# Logic.net
KiCad netlist of a schematic drawn in Altium Designer
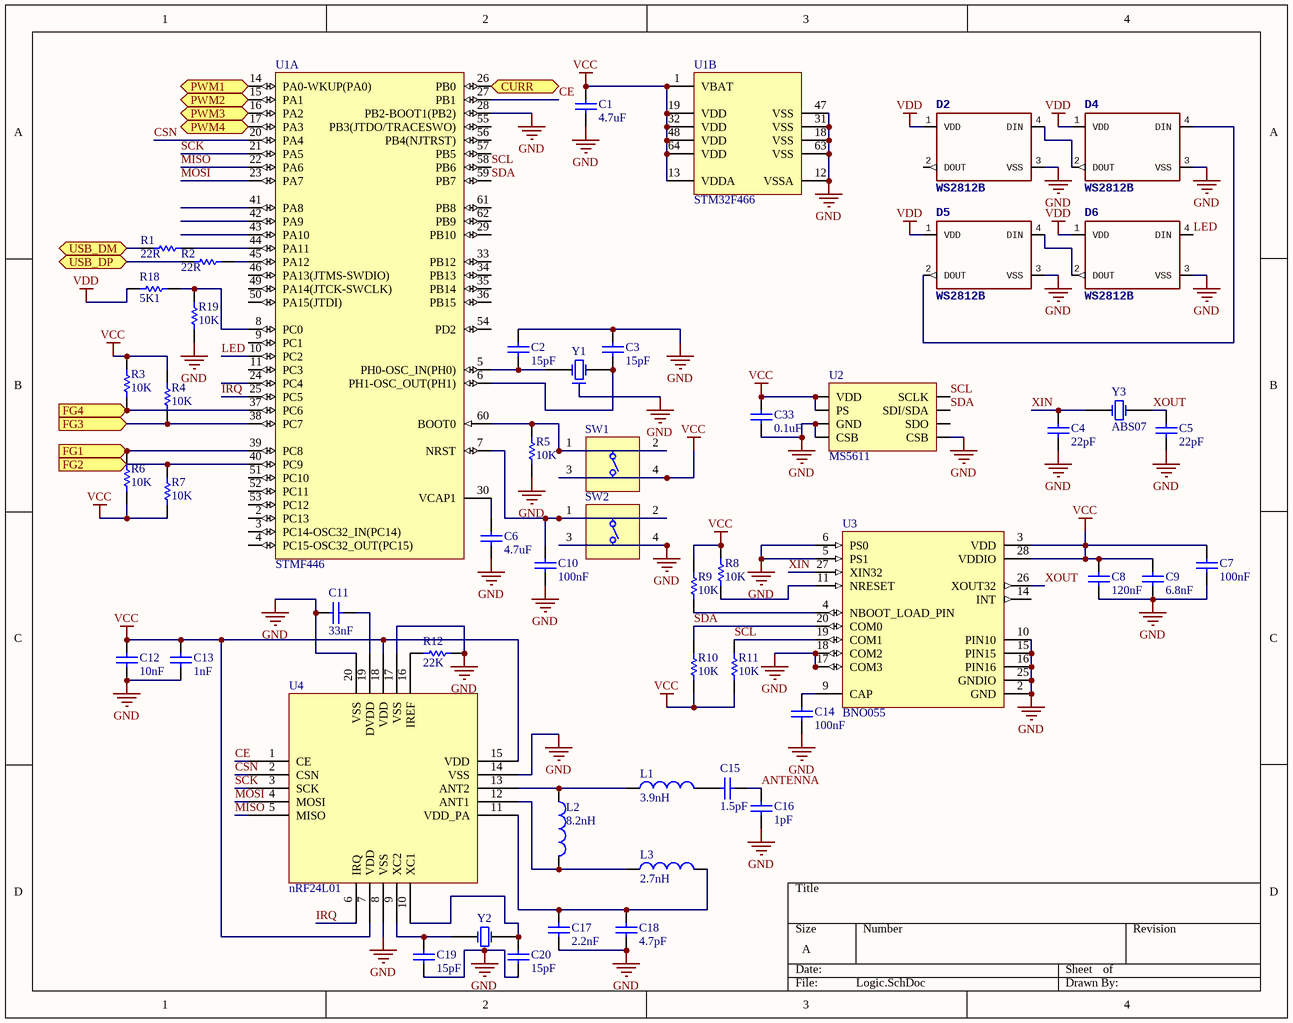
[diagram p0: Logic.SchDoc]

(export (version "E")
  (design (tool "Eeschema 10.0.6"))
  (components
    (comp (ref "C1")
      (value "4.7uF")
      (footprint "CAPC0402(1005)60_L")
      (description "CAP 4.7uF 6.3V ±10% 0402 (1005 Metric) Thickness 0.6mm SMD")
      (fields (field (name "TOLERANCE") "Â±10%"))
      (libsource (lib "Altium Content Vault") (part "CAP"))
    )
    (comp (ref "C2")
      (value "15pF")
      (footprint "CAPC0402(1005)60_M")
      (description "CAP 15pF 25V ±0.25pF 0402 (1005 Metric) Thickness 0.6mm SMD")
      (fields (field (name "TOLERANCE") "Â±0.25pF"))
      (libsource (lib "Altium Content Vault") (part "CMP-1034-00804-1"))
    )
    (comp (ref "C3")
      (value "15pF")
      (footprint "CAPC0402(1005)60_M")
      (description "CAP 15pF 25V ±0.25pF 0402 (1005 Metric) Thickness 0.6mm SMD")
      (fields (field (name "TOLERANCE") "Â±0.25pF"))
      (libsource (lib "Altium Content Vault") (part "CMP-1034-00804-1"))
    )
    (comp (ref "C4")
      (value "22pF")
      (footprint "CAPC0402(1005)60_L")
      (description "CAP 22pF 25V ±10% 0402 (1005 Metric) Thickness 0.6mm SMD")
      (fields (field (name "TOLERANCE") "Â±10%"))
      (libsource (lib "Altium Content Vault") (part "CAP"))
    )
    (comp (ref "C5")
      (value "22pF")
      (footprint "CAPC0402(1005)60_L")
      (description "CAP 22pF 25V ±10% 0402 (1005 Metric) Thickness 0.6mm SMD")
      (fields (field (name "TOLERANCE") "Â±10%"))
      (libsource (lib "Altium Content Vault") (part "CAP"))
    )
    (comp (ref "C6")
      (value "4.7uF")
      (footprint "CAPC0402(1005)60_L")
      (description "CAP 4.7uF 6.3V ±10% 0402 (1005 Metric) Thickness 0.6mm SMD")
      (fields (field (name "TOLERANCE") "Â±10%"))
      (libsource (lib "Altium Content Vault") (part "CMP-1034-02136-1"))
    )
    (comp (ref "C7")
      (value "100nF")
      (footprint "CAPC0402(1005)60_M")
      (description "CAP 100nF 6.3V ±5% 0402 (1005 Metric) Thickness 0.6mm SMD")
      (fields (field (name "TOLERANCE") "Â±5%"))
      (libsource (lib "Altium Content Vault") (part "CAP"))
    )
    (comp (ref "C8")
      (value "120nF")
      (footprint "CAPC0402(1005)60_M")
      (description "CAP 100nF 6.3V ±5% 0402 (1005 Metric) Thickness 0.6mm SMD")
      (fields (field (name "TOLERANCE") "Â±5%"))
      (libsource (lib "Altium Content Vault") (part "CAP"))
    )
    (comp (ref "C9")
      (value "6.8nF")
      (footprint "CAPC0402(1005)60_L")
      (description "CAP 6.8nF 6.3V ±5% 0402 (1005 Metric) Thickness 0.6mm SMD")
      (fields (field (name "TOLERANCE") "Â±5%"))
      (libsource (lib "Altium Content Vault") (part "CAP"))
    )
    (comp (ref "C10")
      (value "100nF")
      (footprint "CAPC0402(1005)60_M")
      (description "CAP 100nF 6.3V ±5% 0402 (1005 Metric) Thickness 0.6mm SMD")
      (fields (field (name "TOLERANCE") "Â±5%"))
      (libsource (lib "Altium Content Vault") (part "CAP"))
    )
    (comp (ref "C11")
      (value "33nF")
      (footprint "CAPC0402(1005)60_M")
      (description "CAP 33nF 6.3V ±10% 0402 (1005 Metric) Thickness 0.6mm SMD")
      (fields (field (name "TOLERANCE") "Â±10%"))
      (libsource (lib "Altium Content Vault") (part "CAP"))
    )
    (comp (ref "C12")
      (value "10nF")
      (footprint "CAPC0402(1005)60_M")
      (description "CAP 10nF 6.3V ±5% 0402 (1005 Metric) Thickness 0.6mm SMD")
      (fields (field (name "TOLERANCE") "Â±5%"))
      (libsource (lib "Altium Content Vault") (part "CAP"))
    )
    (comp (ref "C13")
      (value "1nF")
      (footprint "CAPC0402(1005)60_M")
      (description "CAP 1nF 6.3V ±5% 0402 (1005 Metric) Thickness 0.6mm SMD")
      (fields (field (name "TOLERANCE") "Â±5%"))
      (libsource (lib "Altium Content Vault") (part "CAP"))
    )
    (comp (ref "C14")
      (value "100nF")
      (footprint "CAPC0402(1005)60_M")
      (description "CAP 100nF 6.3V ±5% 0402 (1005 Metric) Thickness 0.6mm SMD")
      (fields (field (name "TOLERANCE") "Â±5%"))
      (libsource (lib "Altium Content Vault") (part "CAP"))
    )
    (comp (ref "C15")
      (value "1.5pF")
      (footprint "CAPC0402(1005)60_L")
      (description "CAP 1.5pF 25V ±0.5pF 0402 (1005 Metric) Thickness 0.6mm SMD")
      (fields (field (name "TOLERANCE") "Â±0.5pF"))
      (libsource (lib "Altium Content Vault") (part "CAP"))
    )
    (comp (ref "C16")
      (value "1pF")
      (footprint "CAPC0402(1005)60_M")
      (description "CAP 1pF 25V ±0.5pF 0402 (1005 Metric) Thickness 0.6mm SMD")
      (fields (field (name "TOLERANCE") "Â±0.5pF"))
      (libsource (lib "Altium Content Vault") (part "CAP"))
    )
    (comp (ref "C17")
      (value "2.2nF")
      (footprint "CAPC0402(1005)60_N")
      (description "CAP 2.2nF 6.3V ±5% 0402 (1005 Metric) Thickness 0.6mm SMD")
      (fields (field (name "TOLERANCE") "Â±5%"))
      (libsource (lib "Altium Content Vault") (part "CAP"))
    )
    (comp (ref "C18")
      (value "4.7pF")
      (footprint "CAPC0402(1005)60_M")
      (description "CAP 4.7pF 25V ±0.1pF 0402 (1005 Metric) Thickness 0.6mm SMD")
      (fields (field (name "TOLERANCE") "Â±0.1pF"))
      (libsource (lib "Altium Content Vault") (part "CAP"))
    )
    (comp (ref "C19")
      (value "15pF")
      (footprint "CAPC0402(1005)60_N")
      (description "CAP 15pF 25V ±10% 0402 (1005 Metric) Thickness 0.6mm SMD")
      (fields (field (name "TOLERANCE") "Â±10%"))
      (libsource (lib "Altium Content Vault") (part "CAP"))
    )
    (comp (ref "C20")
      (value "15pF")
      (footprint "CAPC0402(1005)60_N")
      (description "CAP 15pF 25V ±10% 0402 (1005 Metric) Thickness 0.6mm SMD")
      (fields (field (name "TOLERANCE") "Â±10%"))
      (libsource (lib "Altium Content Vault") (part "CMP-1034-00809-1"))
    )
    (comp (ref "C33")
      (value "0.1uF")
      (footprint "CAPC0402(1005)60_M")
      (description "CAP 100nF 6.3V ±5% 0402 (1005 Metric) Thickness 0.6mm SMD")
      (fields (field (name "TOLERANCE") "Â±5%"))
      (libsource (lib "Altium Content Vault") (part "CAP"))
    )
    (comp (ref "D2") (value "WS2812B") (footprint "WS2812B") (libsource (lib "Components") (part "WS2812B")))
    (comp (ref "D4") (value "WS2812B") (footprint "WS2812B") (libsource (lib "Components") (part "WS2812B")))
    (comp (ref "D5") (value "WS2812B") (footprint "WS2812B") (libsource (lib "Components") (part "WS2812B")))
    (comp (ref "D6") (value "WS2812B") (footprint "WS2812B") (libsource (lib "Components") (part "WS2812B")))
    (comp (ref "L1")
      (value "3.9nH")
      (footprint "INDC0402(1005)_N")
      (description "Inductor")
      (fields (field (name "PUBLISHER") "Altium Limited"))
      (libsource (lib "Components") (part "INDC0402"))
    )
    (comp (ref "L2")
      (value "8.2nH")
      (footprint "INDC0402(1005)_N")
      (description "Inductor")
      (fields (field (name "PUBLISHER") "Altium Limited"))
      (libsource (lib "Components") (part "INDC0402"))
    )
    (comp (ref "L3")
      (value "2.7nH")
      (footprint "INDC0402(1005)_N")
      (description "Inductor")
      (fields (field (name "PUBLISHER") "Altium Limited"))
      (libsource (lib "Components") (part "INDC0402"))
    )
    (comp (ref "R1")
      (value "22R")
      (footprint "RESC0402(1005)_M")
      (description "22R 0.063W 5% 0402 (1005 Metric)  SMD")
      (fields (field (name "POWER") "0.063 W") (field (name "TOLERANCE") "5 %"))
      (libsource (lib "Altium Content Vault") (part "RES"))
    )
    (comp (ref "R2")
      (value "22R")
      (footprint "RESC0402(1005)_M")
      (description "22R 0.063W 5% 0402 (1005 Metric)  SMD")
      (fields (field (name "POWER") "0.063 W") (field (name "TOLERANCE") "5 %"))
      (libsource (lib "Altium Content Vault") (part "RES"))
    )
    (comp (ref "R3")
      (value "10K")
      (footprint "RESC0402(1005)_N")
      (description "10K 0.063W 5% 0402 (1005 Metric)  SMD")
      (fields (field (name "TOLERANCE") "5 %") (field (name "POWER") "0.063 W"))
      (libsource (lib "Altium Content Vault") (part "RES"))
    )
    (comp (ref "R4")
      (value "10K")
      (footprint "RESC0402(1005)_N")
      (description "10K 0.063W 5% 0402 (1005 Metric)  SMD")
      (fields (field (name "TOLERANCE") "5 %") (field (name "POWER") "0.063 W"))
      (libsource (lib "Altium Content Vault") (part "RES"))
    )
    (comp (ref "R5")
      (value "10K")
      (footprint "RESC0402(1005)_N")
      (description "10K 0.063W 5% 0402 (1005 Metric)  SMD")
      (fields (field (name "TOLERANCE") "5 %") (field (name "POWER") "0.063 W"))
      (libsource (lib "Altium Content Vault") (part "RES"))
    )
    (comp (ref "R6")
      (value "10K")
      (footprint "RESC0402(1005)_N")
      (description "10K 0.063W 5% 0402 (1005 Metric)  SMD")
      (fields (field (name "TOLERANCE") "5 %") (field (name "POWER") "0.063 W"))
      (libsource (lib "Altium Content Vault") (part "RES"))
    )
    (comp (ref "R7")
      (value "10K")
      (footprint "RESC0402(1005)_N")
      (description "10K 0.063W 5% 0402 (1005 Metric)  SMD")
      (fields (field (name "TOLERANCE") "5 %") (field (name "POWER") "0.063 W"))
      (libsource (lib "Altium Content Vault") (part "RES"))
    )
    (comp (ref "R8")
      (value "10K")
      (footprint "RESC0402(1005)_N")
      (description "10K 0.063W 5% 0402 (1005 Metric)  SMD")
      (fields (field (name "TOLERANCE") "5 %") (field (name "POWER") "0.063 W"))
      (libsource (lib "Altium Content Vault") (part "RES"))
    )
    (comp (ref "R9")
      (value "10K")
      (footprint "RESC0402(1005)_N")
      (description "10K 0.063W 5% 0402 (1005 Metric)  SMD")
      (fields (field (name "TOLERANCE") "5 %") (field (name "POWER") "0.063 W"))
      (libsource (lib "Altium Content Vault") (part "RES"))
    )
    (comp (ref "R10")
      (value "10K")
      (footprint "RESC0402(1005)_N")
      (description "10K 0.063W 5% 0402 (1005 Metric)  SMD")
      (fields (field (name "TOLERANCE") "5 %") (field (name "POWER") "0.063 W"))
      (libsource (lib "Altium Content Vault") (part "RES"))
    )
    (comp (ref "R11")
      (value "10K")
      (footprint "RESC0402(1005)_N")
      (description "10K 0.063W 5% 0402 (1005 Metric)  SMD")
      (fields (field (name "TOLERANCE") "5 %") (field (name "POWER") "0.063 W"))
      (libsource (lib "Altium Content Vault") (part "RES"))
    )
    (comp (ref "R12")
      (value "22K")
      (footprint "RESC0402(1005)_L")
      (description "22K 0.063W 5% 0402 (1005 Metric)  SMD")
      (fields (field (name "TOLERANCE") "5 %") (field (name "POWER") "0.063 W"))
      (libsource (lib "Altium Content Vault") (part "RES"))
    )
    (comp (ref "R18")
      (value "5K1")
      (footprint "RESC0402(1005)_L")
      (description "5K1 0.063W 5% 0402 (1005 Metric)  SMD")
      (fields (field (name "TOLERANCE") "5 %") (field (name "POWER") "0.063 W"))
      (libsource (lib "Altium Content Vault") (part "RES"))
    )
    (comp (ref "R19")
      (value "10K")
      (footprint "RESC0402(1005)_N")
      (description "10K 0.063W 5% 0402 (1005 Metric)  SMD")
      (fields (field (name "TOLERANCE") "5 %") (field (name "POWER") "0.063 W"))
      (libsource (lib "Altium Content Vault") (part "RES"))
    )
    (comp (ref "SW1")
      (value "~")
      (footprint "SWITCH")
      (description "Switch, SPNO Push Button SMD")
      (fields (field (name "MANUFACTURER") "Diptronics") (field (name "PARTNUMBER") "DTSM-61NT/R"))
      (libsource (lib "altium-import") (part "root_0_DIPT-DTSM-6_"))
    )
    (comp (ref "SW2")
      (value "~")
      (footprint "SWITCH")
      (description "Switch, SPNO Push Button SMD")
      (fields (field (name "MANUFACTURER") "Diptronics") (field (name "PARTNUMBER") "DTSM-61NT/R"))
      (libsource (lib "altium-import") (part "root_0_DIPT-DTSM-6_"))
    )
    (comp (ref "U1")
      (value "STMF446")
      (footprint "STM-LQFP64_N")
      (libsource (lib "Components") (part "MC-ARM-STM32F4X5-SQ64"))
    )
    (comp (ref "U2") (value "MS5611") (footprint "MS5611") (libsource (lib "Components") (part "MS5611")))
    (comp (ref "U3")
      (value "BNO055")
      (footprint "LGA28R50P4X10_380X520X100")
      (libsource (lib "Components") (part "BNO055"))
    )
    (comp (ref "U4") (value "~") (footprint "QFN20") (libsource (lib "Components") (part "NRF24L01+")))
    (comp (ref "Y1")
      (value "~")
      (footprint "ABRA-ABM3B-4_V")
      (libsource (lib "Components") (part "ABRA-ABM3B-4"))
    )
    (comp (ref "Y2")
      (value "~")
      (footprint "ABRA-ABM3B-4_V")
      (libsource (lib "Components") (part "ABRA-ABM3B-4"))
    )
    (comp (ref "Y3") (value "ABS07") (footprint "ABS07") (libsource (lib "Components") (part "ABS07")))
  )
  (nets
    (net (code "1") (name "/ANTENNA") (class "Default")
      (node (ref "C15") (pin "2") (pinfunction "2_2") (pintype "passive"))
      (node (ref "C16") (pin "2") (pinfunction "2_2") (pintype "passive"))
    )
    (net (code "2") (name "/CE") (class "Default")
      (node (ref "U1") (pin "27") (pinfunction "PB1_27") (pintype "bidirectional"))
      (node (ref "U4") (pin "1") (pinfunction "CE_1") (pintype "passive"))
    )
    (net (code "3") (name "/CSN") (class "Default")
      (node (ref "U1") (pin "20") (pinfunction "PA4_20") (pintype "bidirectional"))
      (node (ref "U4") (pin "2") (pinfunction "CSN_2") (pintype "passive"))
    )
    (net (code "4") (name "/CURR") (class "Default")
      (node (ref "U1") (pin "26") (pinfunction "PB0_26") (pintype "bidirectional"))
    )
    (net (code "5") (name "/FG1") (class "Default")
      (node (ref "R6") (pin "2") (pinfunction "2_2") (pintype "passive"))
      (node (ref "U1") (pin "39") (pinfunction "PC8_39") (pintype "bidirectional"))
    )
    (net (code "6") (name "/FG2") (class "Default")
      (node (ref "R7") (pin "2") (pinfunction "2_2") (pintype "passive"))
      (node (ref "U1") (pin "40") (pinfunction "PC9_40") (pintype "bidirectional"))
    )
    (net (code "7") (name "/FG3") (class "Default")
      (node (ref "R4") (pin "1") (pinfunction "1_1") (pintype "passive"))
      (node (ref "U1") (pin "38") (pinfunction "PC7_38") (pintype "bidirectional"))
    )
    (net (code "8") (name "/FG4") (class "Default")
      (node (ref "R3") (pin "1") (pinfunction "1_1") (pintype "passive"))
      (node (ref "U1") (pin "37") (pinfunction "PC6_37") (pintype "bidirectional"))
    )
    (net (code "9") (name "/IRQ") (class "Default")
      (node (ref "U1") (pin "25") (pinfunction "PC5_25") (pintype "bidirectional"))
      (node (ref "U4") (pin "6") (pinfunction "IRQ_6") (pintype "passive"))
    )
    (net (code "10") (name "/LED") (class "Default")
      (node (ref "D6") (pin "4") (pinfunction "DIN_4") (pintype "passive"))
      (node (ref "U1") (pin "10") (pinfunction "PC2_10") (pintype "bidirectional"))
    )
    (net (code "11") (name "/MISO") (class "Default")
      (node (ref "U1") (pin "22") (pinfunction "PA6_22") (pintype "bidirectional"))
      (node (ref "U4") (pin "5") (pinfunction "MISO_5") (pintype "passive"))
    )
    (net (code "12") (name "/MOSI") (class "Default")
      (node (ref "U1") (pin "23") (pinfunction "PA7_23") (pintype "bidirectional"))
      (node (ref "U4") (pin "4") (pinfunction "MOSI_4") (pintype "passive"))
    )
    (net (code "13") (name "/PWM1") (class "Default")
      (node (ref "U1") (pin "14") (pinfunction "PA0-WKUP(PA0)_14") (pintype "bidirectional"))
    )
    (net (code "14") (name "/PWM2") (class "Default")
      (node (ref "U1") (pin "15") (pinfunction "PA1_15") (pintype "bidirectional"))
    )
    (net (code "15") (name "/PWM3") (class "Default")
      (node (ref "U1") (pin "16") (pinfunction "PA2_16") (pintype "bidirectional"))
    )
    (net (code "16") (name "/PWM4") (class "Default")
      (node (ref "U1") (pin "17") (pinfunction "PA3_17") (pintype "bidirectional"))
    )
    (net (code "17") (name "/SCK") (class "Default")
      (node (ref "U1") (pin "21") (pinfunction "PA5_21") (pintype "bidirectional"))
      (node (ref "U4") (pin "3") (pinfunction "SCK_3") (pintype "passive"))
    )
    (net (code "18") (name "/SCL") (class "Default")
      (node (ref "R11") (pin "2") (pinfunction "2_2") (pintype "passive"))
      (node (ref "U1") (pin "58") (pinfunction "PB6_58") (pintype "bidirectional"))
      (node (ref "U2") (pin "8") (pinfunction "SCLK_8") (pintype "passive"))
      (node (ref "U3") (pin "19") (pinfunction "COM1_19") (pintype "bidirectional"))
    )
    (net (code "19") (name "/SDA") (class "Default")
      (node (ref "R10") (pin "2") (pinfunction "2_2") (pintype "passive"))
      (node (ref "U1") (pin "59") (pinfunction "PB7_59") (pintype "bidirectional"))
      (node (ref "U2") (pin "7") (pinfunction "SDI/SDA_7") (pintype "passive"))
      (node (ref "U3") (pin "20") (pinfunction "COM0_20") (pintype "bidirectional"))
    )
    (net (code "20") (name "/USB_DM") (class "Default")
      (node (ref "R1") (pin "1") (pinfunction "1_1") (pintype "passive"))
    )
    (net (code "21") (name "/USB_DP") (class "Default")
      (node (ref "R2") (pin "1") (pinfunction "1_1") (pintype "passive"))
    )
    (net (code "22") (name "/XIN") (class "Default")
      (node (ref "C4") (pin "2") (pinfunction "2_2") (pintype "passive"))
      (node (ref "U3") (pin "27") (pinfunction "XIN32_27") (pintype "input"))
      (node (ref "Y3") (pin "1") (pinfunction "X1_1") (pintype "passive"))
    )
    (net (code "23") (name "/XOUT") (class "Default")
      (node (ref "C5") (pin "2") (pinfunction "2_2") (pintype "passive"))
      (node (ref "U3") (pin "26") (pinfunction "XOUT32_26") (pintype "output"))
      (node (ref "Y3") (pin "2") (pinfunction "X2_2") (pintype "passive"))
    )
    (net (code "24") (name "GND") (class "Default")
      (node (ref "C1") (pin "1") (pinfunction "1_1") (pintype "passive"))
      (node (ref "C10") (pin "1") (pinfunction "1_1") (pintype "passive"))
      (node (ref "C11") (pin "1") (pinfunction "1_1") (pintype "passive"))
      (node (ref "C12") (pin "1") (pinfunction "1_1") (pintype "passive"))
      (node (ref "C13") (pin "1") (pinfunction "1_1") (pintype "passive"))
      (node (ref "C14") (pin "1") (pinfunction "1_1") (pintype "passive"))
      (node (ref "C16") (pin "1") (pinfunction "1_1") (pintype "passive"))
      (node (ref "C17") (pin "1") (pinfunction "1_1") (pintype "passive"))
      (node (ref "C18") (pin "1") (pinfunction "1_1") (pintype "passive"))
      (node (ref "C19") (pin "1") (pinfunction "1_1") (pintype "passive"))
      (node (ref "C2") (pin "2") (pinfunction "2_2") (pintype "passive"))
      (node (ref "C20") (pin "1") (pinfunction "1_1") (pintype "passive"))
      (node (ref "C3") (pin "2") (pinfunction "2_2") (pintype "passive"))
      (node (ref "C33") (pin "1") (pinfunction "1_1") (pintype "passive"))
      (node (ref "C4") (pin "1") (pinfunction "1_1") (pintype "passive"))
      (node (ref "C5") (pin "1") (pinfunction "1_1") (pintype "passive"))
      (node (ref "C6") (pin "1") (pinfunction "1_1") (pintype "passive"))
      (node (ref "C7") (pin "1") (pinfunction "1_1") (pintype "passive"))
      (node (ref "C8") (pin "1") (pinfunction "1_1") (pintype "passive"))
      (node (ref "C9") (pin "1") (pinfunction "1_1") (pintype "passive"))
      (node (ref "D2") (pin "3") (pinfunction "VSS_3") (pintype "power_in"))
      (node (ref "D4") (pin "3") (pinfunction "VSS_3") (pintype "power_in"))
      (node (ref "D5") (pin "3") (pinfunction "VSS_3") (pintype "power_in"))
      (node (ref "D6") (pin "3") (pinfunction "VSS_3") (pintype "power_in"))
      (node (ref "R12") (pin "1") (pinfunction "1_1") (pintype "passive"))
      (node (ref "R19") (pin "1") (pinfunction "1_1") (pintype "passive"))
      (node (ref "R5") (pin "1") (pinfunction "1_1") (pintype "passive"))
      (node (ref "SW2") (pin "3") (pinfunction "T3_3") (pintype "passive"))
      (node (ref "SW2") (pin "4") (pinfunction "T3_4") (pintype "passive"))
      (node (ref "U1") (pin "12") (pinfunction "VSSA_12") (pintype "power_in"))
      (node (ref "U1") (pin "18") (pinfunction "VSS_18") (pintype "power_in"))
      (node (ref "U1") (pin "28") (pinfunction "PB2-BOOT1(PB2)_28") (pintype "bidirectional"))
      (node (ref "U1") (pin "31") (pinfunction "VSS_31") (pintype "power_in"))
      (node (ref "U1") (pin "47") (pinfunction "VSS_47") (pintype "power_in"))
      (node (ref "U1") (pin "63") (pinfunction "VSS_63") (pintype "power_in"))
      (node (ref "U2") (pin "3") (pinfunction "GND_3") (pintype "passive"))
      (node (ref "U2") (pin "4") (pinfunction "CSB_4") (pintype "passive"))
      (node (ref "U2") (pin "5") (pinfunction "CSB_5") (pintype "passive"))
      (node (ref "U3") (pin "10") (pinfunction "PIN10_10") (pintype "power_in"))
      (node (ref "U3") (pin "15") (pinfunction "PIN15_15") (pintype "power_in"))
      (node (ref "U3") (pin "16") (pinfunction "PIN16_16") (pintype "power_in"))
      (node (ref "U3") (pin "17") (pinfunction "COM3_17") (pintype "bidirectional"))
      (node (ref "U3") (pin "18") (pinfunction "COM2_18") (pintype "bidirectional"))
      (node (ref "U3") (pin "2") (pinfunction "GND_2") (pintype "power_in"))
      (node (ref "U3") (pin "25") (pinfunction "GNDIO_25") (pintype "power_in"))
      (node (ref "U3") (pin "5") (pinfunction "PS1_5") (pintype "input"))
      (node (ref "U3") (pin "6") (pinfunction "PS0_6") (pintype "input"))
      (node (ref "U4") (pin "14") (pinfunction "VSS_14") (pintype "passive"))
      (node (ref "U4") (pin "17") (pinfunction "VSS_17") (pintype "passive"))
      (node (ref "U4") (pin "20") (pinfunction "VSS_20") (pintype "passive"))
      (node (ref "U4") (pin "8") (pinfunction "VSS_8") (pintype "passive"))
      (node (ref "Y1") (pin "2") (pinfunction "2_2") (pintype "passive"))
      (node (ref "Y2") (pin "2") (pinfunction "2_2") (pintype "passive"))
    )
    (net (code "25") (name "Net-(C15-Pad1)") (class "Default")
      (node (ref "C15") (pin "1") (pinfunction "1_1") (pintype "passive"))
      (node (ref "L1") (pin "2") (pinfunction "2_2") (pintype "passive"))
    )
    (net (code "26") (name "Net-(D2-DIN)") (class "Default")
      (node (ref "D2") (pin "4") (pinfunction "DIN_4") (pintype "passive"))
      (node (ref "D4") (pin "2") (pinfunction "DOUT_2") (pintype "output"))
    )
    (net (code "27") (name "Net-(D4-DIN)") (class "Default")
      (node (ref "D4") (pin "4") (pinfunction "DIN_4") (pintype "passive"))
      (node (ref "D5") (pin "2") (pinfunction "DOUT_2") (pintype "output"))
    )
    (net (code "28") (name "Net-(D5-DIN)") (class "Default")
      (node (ref "D5") (pin "4") (pinfunction "DIN_4") (pintype "passive"))
      (node (ref "D6") (pin "2") (pinfunction "DOUT_2") (pintype "output"))
    )
    (net (code "29") (name "Net-(SW1-T1)") (class "Default")
      (node (ref "R5") (pin "2") (pinfunction "2_2") (pintype "passive"))
      (node (ref "SW1") (pin "1") (pinfunction "T1_1") (pintype "passive"))
      (node (ref "SW1") (pin "2") (pinfunction "T2_2") (pintype "passive"))
      (node (ref "U1") (pin "60") (pinfunction "BOOT0_60") (pintype "input"))
    )
    (net (code "30") (name "Net-(SW2-T1)") (class "Default")
      (node (ref "C10") (pin "2") (pinfunction "2_2") (pintype "passive"))
      (node (ref "SW2") (pin "1") (pinfunction "T1_1") (pintype "passive"))
      (node (ref "SW2") (pin "2") (pinfunction "T2_2") (pintype "passive"))
      (node (ref "U1") (pin "7") (pinfunction "NRST_7") (pintype "bidirectional"))
    )
    (net (code "31") (name "Net-(U1A-PA11)") (class "Default")
      (node (ref "R1") (pin "2") (pinfunction "2_2") (pintype "passive"))
      (node (ref "U1") (pin "44") (pinfunction "PA11_44") (pintype "bidirectional"))
    )
    (net (code "32") (name "Net-(U1A-PA12)") (class "Default")
      (node (ref "R2") (pin "2") (pinfunction "2_2") (pintype "passive"))
      (node (ref "U1") (pin "45") (pinfunction "PA12_45") (pintype "bidirectional"))
    )
    (net (code "33") (name "Net-(U1A-PC0)") (class "Default")
      (node (ref "R18") (pin "1") (pinfunction "1_1") (pintype "passive"))
      (node (ref "R19") (pin "2") (pinfunction "2_2") (pintype "passive"))
      (node (ref "U1") (pin "8") (pinfunction "PC0_8") (pintype "bidirectional"))
    )
    (net (code "34") (name "Net-(U1A-PH0-OSC_IN(PH0))") (class "Default")
      (node (ref "C2") (pin "1") (pinfunction "1_1") (pintype "passive"))
      (node (ref "U1") (pin "5") (pinfunction "PH0-OSC_IN(PH0)_5") (pintype "bidirectional"))
      (node (ref "Y1") (pin "1") (pinfunction "X1_1") (pintype "passive"))
    )
    (net (code "35") (name "Net-(U1A-PH1-OSC_OUT(PH1))") (class "Default")
      (node (ref "C3") (pin "1") (pinfunction "1_1") (pintype "passive"))
      (node (ref "U1") (pin "6") (pinfunction "PH1-OSC_OUT(PH1)_6") (pintype "bidirectional"))
      (node (ref "Y1") (pin "3") (pinfunction "X2_3") (pintype "passive"))
    )
    (net (code "36") (name "Net-(U1A-VCAP1)") (class "Default")
      (node (ref "C6") (pin "2") (pinfunction "2_2") (pintype "passive"))
      (node (ref "U1") (pin "30") (pinfunction "VCAP1_30") (pintype "power_in"))
    )
    (net (code "37") (name "Net-(U3-CAP)") (class "Default")
      (node (ref "C14") (pin "2") (pinfunction "2_2") (pintype "passive"))
      (node (ref "U3") (pin "9") (pinfunction "CAP_9") (pintype "passive"))
    )
    (net (code "38") (name "Net-(U3-NBOOT_LOAD_PIN)") (class "Default")
      (node (ref "R9") (pin "1") (pinfunction "1_1") (pintype "passive"))
      (node (ref "U3") (pin "4") (pinfunction "NBOOT_LOAD_PIN_4") (pintype "bidirectional"))
    )
    (net (code "39") (name "Net-(U3-NRESET)") (class "Default")
      (node (ref "R8") (pin "1") (pinfunction "1_1") (pintype "passive"))
      (node (ref "U3") (pin "11") (pinfunction "NRESET_11") (pintype "input"))
    )
    (net (code "40") (name "Net-(U4-ANT1)") (class "Default")
      (node (ref "L2") (pin "2") (pinfunction "2_2") (pintype "passive"))
      (node (ref "L3") (pin "1") (pinfunction "1_1") (pintype "passive"))
      (node (ref "U4") (pin "12") (pinfunction "ANT1_12") (pintype "passive"))
    )
    (net (code "41") (name "Net-(U4-ANT2)") (class "Default")
      (node (ref "L1") (pin "1") (pinfunction "1_1") (pintype "passive"))
      (node (ref "L2") (pin "1") (pinfunction "1_1") (pintype "passive"))
      (node (ref "U4") (pin "13") (pinfunction "ANT2_13") (pintype "passive"))
    )
    (net (code "42") (name "Net-(U4-DVDD)") (class "Default")
      (node (ref "C11") (pin "2") (pinfunction "2_2") (pintype "passive"))
      (node (ref "U4") (pin "19") (pinfunction "DVDD_19") (pintype "passive"))
    )
    (net (code "43") (name "Net-(U4-IREF)") (class "Default")
      (node (ref "R12") (pin "2") (pinfunction "2_2") (pintype "passive"))
      (node (ref "U4") (pin "16") (pinfunction "IREF_16") (pintype "passive"))
    )
    (net (code "44") (name "Net-(U4-VDD_PA)") (class "Default")
      (node (ref "C17") (pin "2") (pinfunction "2_2") (pintype "passive"))
      (node (ref "C18") (pin "2") (pinfunction "2_2") (pintype "passive"))
      (node (ref "L3") (pin "2") (pinfunction "2_2") (pintype "passive"))
      (node (ref "U4") (pin "11") (pinfunction "VDD_PA_11") (pintype "passive"))
    )
    (net (code "45") (name "Net-(U4-XC1)") (class "Default")
      (node (ref "C20") (pin "2") (pinfunction "2_2") (pintype "passive"))
      (node (ref "U4") (pin "10") (pinfunction "XC1_10") (pintype "passive"))
      (node (ref "Y2") (pin "3") (pinfunction "X2_3") (pintype "passive"))
    )
    (net (code "46") (name "Net-(U4-XC2)") (class "Default")
      (node (ref "C19") (pin "2") (pinfunction "2_2") (pintype "passive"))
      (node (ref "U4") (pin "9") (pinfunction "XC2_9") (pintype "passive"))
      (node (ref "Y2") (pin "1") (pinfunction "X1_1") (pintype "passive"))
    )
    (net (code "47") (name "VCC") (class "Default")
      (node (ref "C1") (pin "2") (pinfunction "2_2") (pintype "passive"))
      (node (ref "C12") (pin "2") (pinfunction "2_2") (pintype "passive"))
      (node (ref "C13") (pin "2") (pinfunction "2_2") (pintype "passive"))
      (node (ref "C33") (pin "2") (pinfunction "2_2") (pintype "passive"))
      (node (ref "C7") (pin "2") (pinfunction "2_2") (pintype "passive"))
      (node (ref "C8") (pin "2") (pinfunction "2_2") (pintype "passive"))
      (node (ref "C9") (pin "2") (pinfunction "2_2") (pintype "passive"))
      (node (ref "R10") (pin "1") (pinfunction "1_1") (pintype "passive"))
      (node (ref "R11") (pin "1") (pinfunction "1_1") (pintype "passive"))
      (node (ref "R3") (pin "2") (pinfunction "2_2") (pintype "passive"))
      (node (ref "R4") (pin "2") (pinfunction "2_2") (pintype "passive"))
      (node (ref "R6") (pin "1") (pinfunction "1_1") (pintype "passive"))
      (node (ref "R7") (pin "1") (pinfunction "1_1") (pintype "passive"))
      (node (ref "R8") (pin "2") (pinfunction "2_2") (pintype "passive"))
      (node (ref "R9") (pin "2") (pinfunction "2_2") (pintype "passive"))
      (node (ref "SW1") (pin "3") (pinfunction "T3_3") (pintype "passive"))
      (node (ref "SW1") (pin "4") (pinfunction "T3_4") (pintype "passive"))
      (node (ref "U1") (pin "1") (pinfunction "VBAT_1") (pintype "power_in"))
      (node (ref "U1") (pin "13") (pinfunction "VDDA_13") (pintype "power_in"))
      (node (ref "U1") (pin "19") (pinfunction "VDD_19") (pintype "power_in"))
      (node (ref "U1") (pin "32") (pinfunction "VDD_32") (pintype "power_in"))
      (node (ref "U1") (pin "48") (pinfunction "VDD_48") (pintype "power_in"))
      (node (ref "U1") (pin "64") (pinfunction "VDD_64") (pintype "power_in"))
      (node (ref "U2") (pin "1") (pinfunction "VDD_1") (pintype "passive"))
      (node (ref "U2") (pin "2") (pinfunction "PS_2") (pintype "passive"))
      (node (ref "U3") (pin "28") (pinfunction "VDDIO_28") (pintype "power_in"))
      (node (ref "U3") (pin "3") (pinfunction "VDD_3") (pintype "power_in"))
      (node (ref "U4") (pin "15") (pinfunction "VDD_15") (pintype "passive"))
      (node (ref "U4") (pin "18") (pinfunction "VDD_18") (pintype "passive"))
      (node (ref "U4") (pin "7") (pinfunction "VDD_7") (pintype "passive"))
    )
    (net (code "48") (name "VDD") (class "Default")
      (node (ref "D2") (pin "1") (pinfunction "VDD_1") (pintype "power_in"))
      (node (ref "D4") (pin "1") (pinfunction "VDD_1") (pintype "power_in"))
      (node (ref "D5") (pin "1") (pinfunction "VDD_1") (pintype "power_in"))
      (node (ref "D6") (pin "1") (pinfunction "VDD_1") (pintype "power_in"))
      (node (ref "R18") (pin "2") (pinfunction "2_2") (pintype "passive"))
    )
    (net (code "49") (name "unconnected-(D2-DOUT-Pad2)") (class "Default")
      (node (ref "D2") (pin "2") (pinfunction "DOUT_2") (pintype "output"))
    )
    (net (code "50") (name "unconnected-(U1A-PA8-Pad41)") (class "Default")
      (node (ref "U1") (pin "41") (pinfunction "PA8_41") (pintype "bidirectional"))
    )
    (net (code "51") (name "unconnected-(U1A-PA9-Pad42)") (class "Default")
      (node (ref "U1") (pin "42") (pinfunction "PA9_42") (pintype "bidirectional"))
    )
    (net (code "52") (name "unconnected-(U1A-PA10-Pad43)") (class "Default")
      (node (ref "U1") (pin "43") (pinfunction "PA10_43") (pintype "bidirectional"))
    )
    (net (code "53") (name "unconnected-(U1A-PA13(JTMS-SWDIO)-Pad46)") (class "Default")
      (node (ref "U1") (pin "46") (pinfunction "PA13(JTMS-SWDIO)_46") (pintype "bidirectional"))
    )
    (net (code "54") (name "unconnected-(U1A-PA14(JTCK-SWCLK)-Pad49)") (class "Default")
      (node (ref "U1") (pin "49") (pinfunction "PA14(JTCK-SWCLK)_49") (pintype "bidirectional"))
    )
    (net (code "55") (name "unconnected-(U1A-PA15(JTDI)-Pad50)") (class "Default")
      (node (ref "U1") (pin "50") (pinfunction "PA15(JTDI)_50") (pintype "bidirectional"))
    )
    (net (code "56") (name "unconnected-(U1A-PB3(JTDO{slash}TRACESWO)-Pad55)") (class "Default")
      (node (ref "U1") (pin "55") (pinfunction "PB3(JTDO/TRACESWO)_55") (pintype "bidirectional"))
    )
    (net (code "57") (name "unconnected-(U1A-PB4(NJTRST)-Pad56)") (class "Default")
      (node (ref "U1") (pin "56") (pinfunction "PB4(NJTRST)_56") (pintype "bidirectional"))
    )
    (net (code "58") (name "unconnected-(U1A-PB5-Pad57)") (class "Default")
      (node (ref "U1") (pin "57") (pinfunction "PB5_57") (pintype "bidirectional"))
    )
    (net (code "59") (name "unconnected-(U1A-PB8-Pad61)") (class "Default")
      (node (ref "U1") (pin "61") (pinfunction "PB8_61") (pintype "bidirectional"))
    )
    (net (code "60") (name "unconnected-(U1A-PB9-Pad62)") (class "Default")
      (node (ref "U1") (pin "62") (pinfunction "PB9_62") (pintype "bidirectional"))
    )
    (net (code "61") (name "unconnected-(U1A-PB10-Pad29)") (class "Default")
      (node (ref "U1") (pin "29") (pinfunction "PB10_29") (pintype "bidirectional"))
    )
    (net (code "62") (name "unconnected-(U1A-PB12-Pad33)") (class "Default")
      (node (ref "U1") (pin "33") (pinfunction "PB12_33") (pintype "bidirectional"))
    )
    (net (code "63") (name "unconnected-(U1A-PB13-Pad34)") (class "Default")
      (node (ref "U1") (pin "34") (pinfunction "PB13_34") (pintype "bidirectional"))
    )
    (net (code "64") (name "unconnected-(U1A-PB14-Pad35)") (class "Default")
      (node (ref "U1") (pin "35") (pinfunction "PB14_35") (pintype "bidirectional"))
    )
    (net (code "65") (name "unconnected-(U1A-PB15-Pad36)") (class "Default")
      (node (ref "U1") (pin "36") (pinfunction "PB15_36") (pintype "bidirectional"))
    )
    (net (code "66") (name "unconnected-(U1A-PC1-Pad9)") (class "Default")
      (node (ref "U1") (pin "9") (pinfunction "PC1_9") (pintype "bidirectional"))
    )
    (net (code "67") (name "unconnected-(U1A-PC3-Pad11)") (class "Default")
      (node (ref "U1") (pin "11") (pinfunction "PC3_11") (pintype "bidirectional"))
    )
    (net (code "68") (name "unconnected-(U1A-PC4-Pad24)") (class "Default")
      (node (ref "U1") (pin "24") (pinfunction "PC4_24") (pintype "bidirectional"))
    )
    (net (code "69") (name "unconnected-(U1A-PC10-Pad51)") (class "Default")
      (node (ref "U1") (pin "51") (pinfunction "PC10_51") (pintype "bidirectional"))
    )
    (net (code "70") (name "unconnected-(U1A-PC11-Pad52)") (class "Default")
      (node (ref "U1") (pin "52") (pinfunction "PC11_52") (pintype "bidirectional"))
    )
    (net (code "71") (name "unconnected-(U1A-PC12-Pad53)") (class "Default")
      (node (ref "U1") (pin "53") (pinfunction "PC12_53") (pintype "bidirectional"))
    )
    (net (code "72") (name "unconnected-(U1A-PC13-Pad2)") (class "Default")
      (node (ref "U1") (pin "2") (pinfunction "PC13_2") (pintype "bidirectional"))
    )
    (net (code "73") (name "unconnected-(U1A-PC14-OSC32_IN(PC14)-Pad3)") (class "Default")
      (node (ref "U1") (pin "3") (pinfunction "PC14-OSC32_IN(PC14)_3") (pintype "bidirectional"))
    )
    (net (code "74") (name "unconnected-(U1A-PC15-OSC32_OUT(PC15)-Pad4)") (class "Default")
      (node (ref "U1") (pin "4") (pinfunction "PC15-OSC32_OUT(PC15)_4") (pintype "bidirectional"))
    )
    (net (code "75") (name "unconnected-(U1A-PD2-Pad54)") (class "Default")
      (node (ref "U1") (pin "54") (pinfunction "PD2_54") (pintype "bidirectional"))
    )
    (net (code "76") (name "unconnected-(U2-SDO-Pad6)") (class "Default")
      (node (ref "U2") (pin "6") (pinfunction "SDO_6") (pintype "passive"))
    )
    (net (code "77") (name "unconnected-(U3-INT-Pad14)") (class "Default")
      (node (ref "U3") (pin "14") (pinfunction "INT_14") (pintype "output"))
    )
  )
)
